# ChromDot_Ring_two_inch.net
KiCad netlist of a schematic drawn in EAGLE
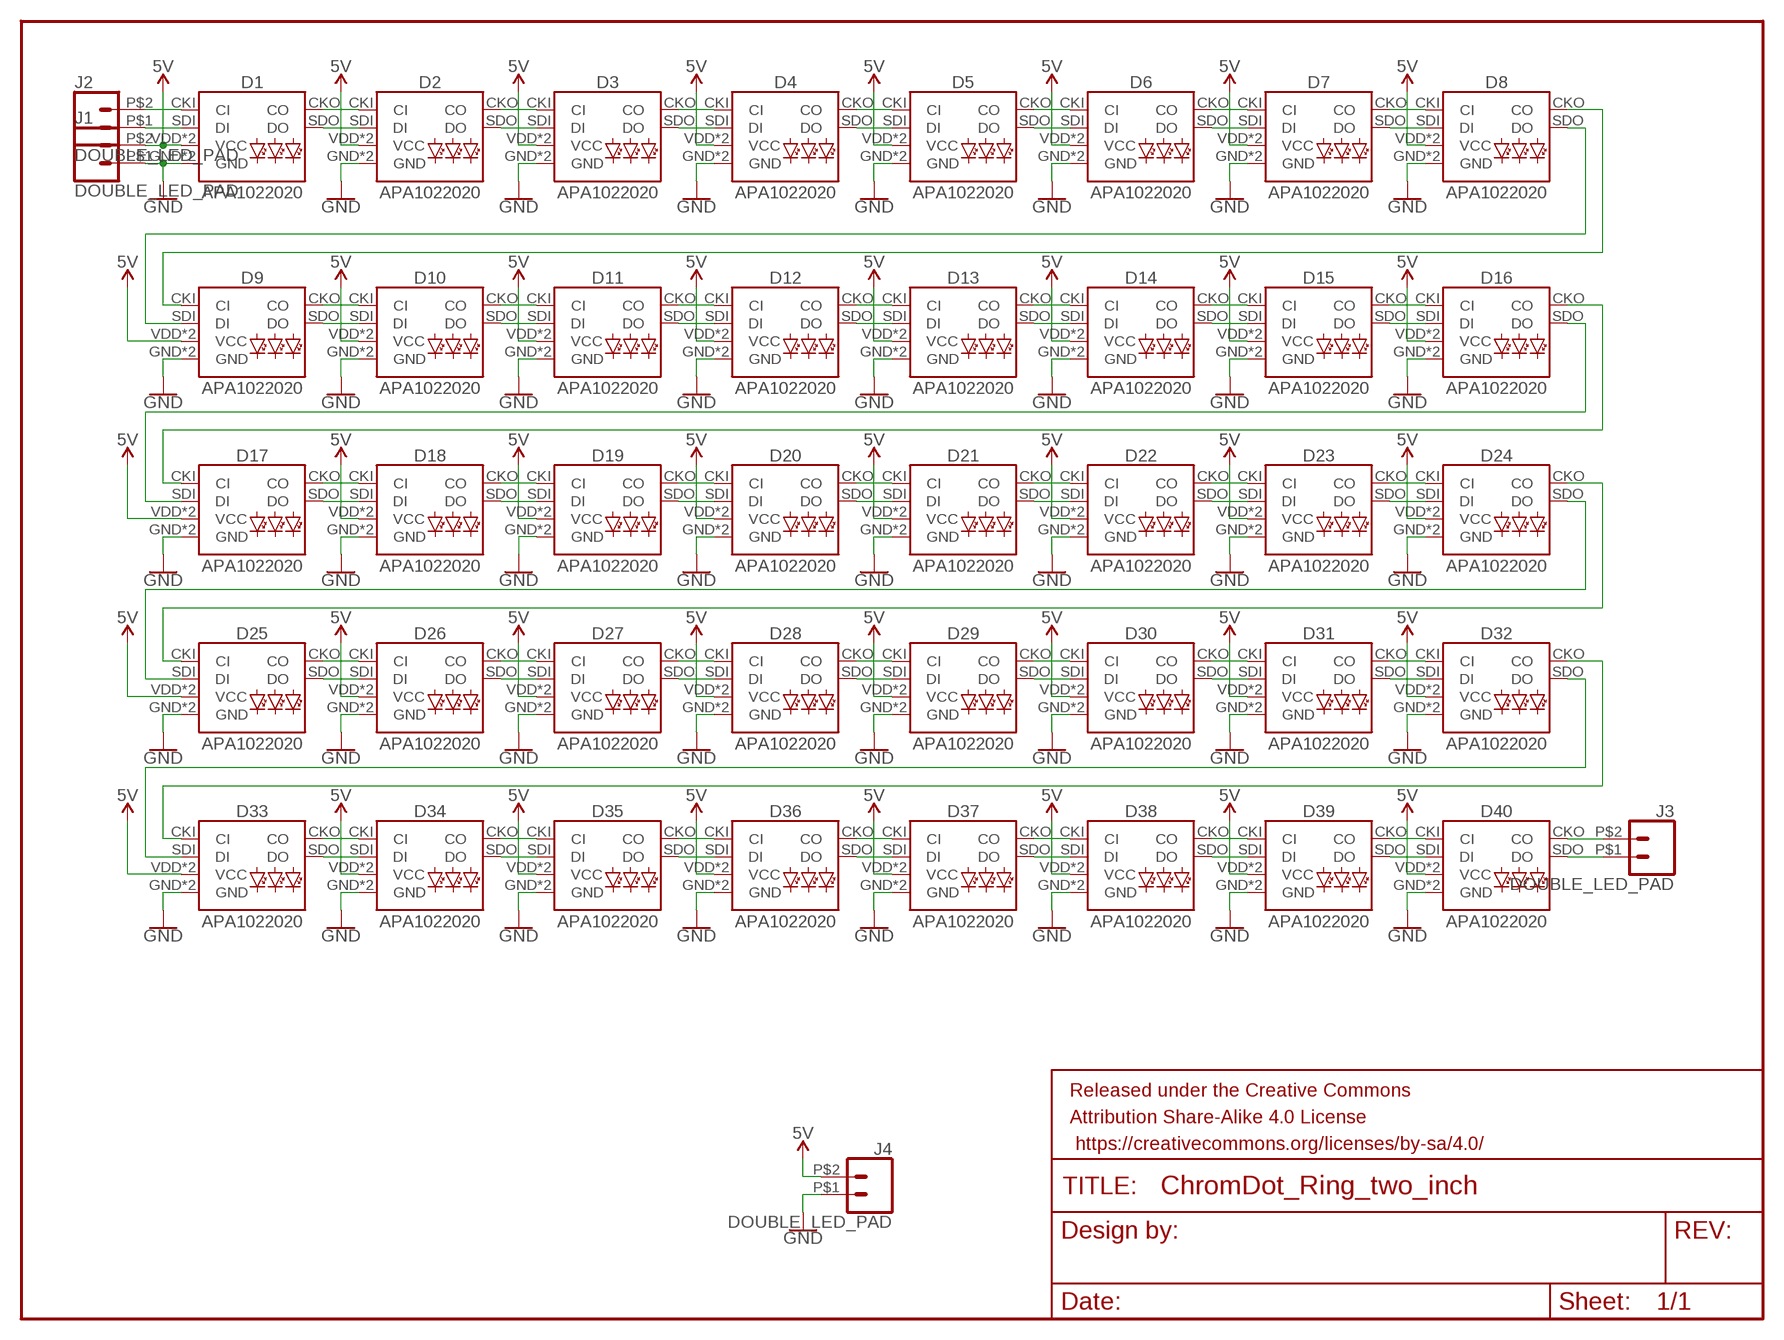
[diagram p0: schematic, sheet 1]

(export (version "E")
  (design (tool "Eeschema 10.0.6"))
  (components
    (comp (ref "D1")
      (value "APA1022020")
      (footprint "eagle-import:APA102-2020")
      (libsource (lib "eagle-import") (part "APA1022020"))
    )
    (comp (ref "D2")
      (value "APA1022020")
      (footprint "eagle-import:APA102-2020")
      (libsource (lib "eagle-import") (part "APA1022020"))
    )
    (comp (ref "D3")
      (value "APA1022020")
      (footprint "eagle-import:APA102-2020")
      (libsource (lib "eagle-import") (part "APA1022020"))
    )
    (comp (ref "D4")
      (value "APA1022020")
      (footprint "eagle-import:APA102-2020")
      (libsource (lib "eagle-import") (part "APA1022020"))
    )
    (comp (ref "D5")
      (value "APA1022020")
      (footprint "eagle-import:APA102-2020")
      (libsource (lib "eagle-import") (part "APA1022020"))
    )
    (comp (ref "D6")
      (value "APA1022020")
      (footprint "eagle-import:APA102-2020")
      (libsource (lib "eagle-import") (part "APA1022020"))
    )
    (comp (ref "D7")
      (value "APA1022020")
      (footprint "eagle-import:APA102-2020")
      (libsource (lib "eagle-import") (part "APA1022020"))
    )
    (comp (ref "D8")
      (value "APA1022020")
      (footprint "eagle-import:APA102-2020")
      (libsource (lib "eagle-import") (part "APA1022020"))
    )
    (comp (ref "D9")
      (value "APA1022020")
      (footprint "eagle-import:APA102-2020")
      (libsource (lib "eagle-import") (part "APA1022020"))
    )
    (comp (ref "D10")
      (value "APA1022020")
      (footprint "eagle-import:APA102-2020")
      (libsource (lib "eagle-import") (part "APA1022020"))
    )
    (comp (ref "D11")
      (value "APA1022020")
      (footprint "eagle-import:APA102-2020")
      (libsource (lib "eagle-import") (part "APA1022020"))
    )
    (comp (ref "D12")
      (value "APA1022020")
      (footprint "eagle-import:APA102-2020")
      (libsource (lib "eagle-import") (part "APA1022020"))
    )
    (comp (ref "D13")
      (value "APA1022020")
      (footprint "eagle-import:APA102-2020")
      (libsource (lib "eagle-import") (part "APA1022020"))
    )
    (comp (ref "D14")
      (value "APA1022020")
      (footprint "eagle-import:APA102-2020")
      (libsource (lib "eagle-import") (part "APA1022020"))
    )
    (comp (ref "D15")
      (value "APA1022020")
      (footprint "eagle-import:APA102-2020")
      (libsource (lib "eagle-import") (part "APA1022020"))
    )
    (comp (ref "D16")
      (value "APA1022020")
      (footprint "eagle-import:APA102-2020")
      (libsource (lib "eagle-import") (part "APA1022020"))
    )
    (comp (ref "D17")
      (value "APA1022020")
      (footprint "eagle-import:APA102-2020")
      (libsource (lib "eagle-import") (part "APA1022020"))
    )
    (comp (ref "D18")
      (value "APA1022020")
      (footprint "eagle-import:APA102-2020")
      (libsource (lib "eagle-import") (part "APA1022020"))
    )
    (comp (ref "D19")
      (value "APA1022020")
      (footprint "eagle-import:APA102-2020")
      (libsource (lib "eagle-import") (part "APA1022020"))
    )
    (comp (ref "D20")
      (value "APA1022020")
      (footprint "eagle-import:APA102-2020")
      (libsource (lib "eagle-import") (part "APA1022020"))
    )
    (comp (ref "D21")
      (value "APA1022020")
      (footprint "eagle-import:APA102-2020")
      (libsource (lib "eagle-import") (part "APA1022020"))
    )
    (comp (ref "D22")
      (value "APA1022020")
      (footprint "eagle-import:APA102-2020")
      (libsource (lib "eagle-import") (part "APA1022020"))
    )
    (comp (ref "D23")
      (value "APA1022020")
      (footprint "eagle-import:APA102-2020")
      (libsource (lib "eagle-import") (part "APA1022020"))
    )
    (comp (ref "D24")
      (value "APA1022020")
      (footprint "eagle-import:APA102-2020")
      (libsource (lib "eagle-import") (part "APA1022020"))
    )
    (comp (ref "D25")
      (value "APA1022020")
      (footprint "eagle-import:APA102-2020")
      (libsource (lib "eagle-import") (part "APA1022020"))
    )
    (comp (ref "D26")
      (value "APA1022020")
      (footprint "eagle-import:APA102-2020")
      (libsource (lib "eagle-import") (part "APA1022020"))
    )
    (comp (ref "D27")
      (value "APA1022020")
      (footprint "eagle-import:APA102-2020")
      (libsource (lib "eagle-import") (part "APA1022020"))
    )
    (comp (ref "D28")
      (value "APA1022020")
      (footprint "eagle-import:APA102-2020")
      (libsource (lib "eagle-import") (part "APA1022020"))
    )
    (comp (ref "D29")
      (value "APA1022020")
      (footprint "eagle-import:APA102-2020")
      (libsource (lib "eagle-import") (part "APA1022020"))
    )
    (comp (ref "D30")
      (value "APA1022020")
      (footprint "eagle-import:APA102-2020")
      (libsource (lib "eagle-import") (part "APA1022020"))
    )
    (comp (ref "D31")
      (value "APA1022020")
      (footprint "eagle-import:APA102-2020")
      (libsource (lib "eagle-import") (part "APA1022020"))
    )
    (comp (ref "D32")
      (value "APA1022020")
      (footprint "eagle-import:APA102-2020")
      (libsource (lib "eagle-import") (part "APA1022020"))
    )
    (comp (ref "D33")
      (value "APA1022020")
      (footprint "eagle-import:APA102-2020")
      (libsource (lib "eagle-import") (part "APA1022020"))
    )
    (comp (ref "D34")
      (value "APA1022020")
      (footprint "eagle-import:APA102-2020")
      (libsource (lib "eagle-import") (part "APA1022020"))
    )
    (comp (ref "D35")
      (value "APA1022020")
      (footprint "eagle-import:APA102-2020")
      (libsource (lib "eagle-import") (part "APA1022020"))
    )
    (comp (ref "D36")
      (value "APA1022020")
      (footprint "eagle-import:APA102-2020")
      (libsource (lib "eagle-import") (part "APA1022020"))
    )
    (comp (ref "D37")
      (value "APA1022020")
      (footprint "eagle-import:APA102-2020")
      (libsource (lib "eagle-import") (part "APA1022020"))
    )
    (comp (ref "D38")
      (value "APA1022020")
      (footprint "eagle-import:APA102-2020")
      (libsource (lib "eagle-import") (part "APA1022020"))
    )
    (comp (ref "D39")
      (value "APA1022020")
      (footprint "eagle-import:APA102-2020")
      (libsource (lib "eagle-import") (part "APA1022020"))
    )
    (comp (ref "D40")
      (value "APA1022020")
      (footprint "eagle-import:APA102-2020")
      (libsource (lib "eagle-import") (part "APA1022020"))
    )
    (comp (ref "FRAME1")
      (value "FRAME-LETTER")
      (footprint "eagle-import:CREATIVE_COMMONS")
      (libsource (lib "eagle-import") (part "FRAME-LETTER"))
    )
    (comp (ref "J1")
      (value "DOUBLE_LED_PAD")
      (footprint "eagle-import:DOUBLELEDPAD")
      (libsource (lib "eagle-import") (part "DOUBLE_LED_PAD"))
    )
    (comp (ref "J2")
      (value "DOUBLE_LED_PAD")
      (footprint "eagle-import:DOUBLELEDPAD")
      (libsource (lib "eagle-import") (part "DOUBLE_LED_PAD"))
    )
    (comp (ref "J3")
      (value "DOUBLE_LED_PAD")
      (footprint "eagle-import:DOUBLELEDPAD")
      (libsource (lib "eagle-import") (part "DOUBLE_LED_PAD"))
    )
    (comp (ref "J4")
      (value "DOUBLE_LED_PAD")
      (footprint "eagle-import:DOUBLELEDPAD")
      (libsource (lib "eagle-import") (part "DOUBLE_LED_PAD"))
    )
  )
  (nets
    (net (code "1") (name "5V") (class "Default")
      (node (ref "D1") (pin "VDD") (pinfunction "VCC_VDD") (pintype "bidirectional"))
      (node (ref "D1") (pin "VDDPAD") (pinfunction "VCC_VDDPAD") (pintype "bidirectional"))
      (node (ref "D10") (pin "VDD") (pinfunction "VCC_VDD") (pintype "bidirectional"))
      (node (ref "D10") (pin "VDDPAD") (pinfunction "VCC_VDDPAD") (pintype "bidirectional"))
      (node (ref "D11") (pin "VDD") (pinfunction "VCC_VDD") (pintype "bidirectional"))
      (node (ref "D11") (pin "VDDPAD") (pinfunction "VCC_VDDPAD") (pintype "bidirectional"))
      (node (ref "D12") (pin "VDD") (pinfunction "VCC_VDD") (pintype "bidirectional"))
      (node (ref "D12") (pin "VDDPAD") (pinfunction "VCC_VDDPAD") (pintype "bidirectional"))
      (node (ref "D13") (pin "VDD") (pinfunction "VCC_VDD") (pintype "bidirectional"))
      (node (ref "D13") (pin "VDDPAD") (pinfunction "VCC_VDDPAD") (pintype "bidirectional"))
      (node (ref "D14") (pin "VDD") (pinfunction "VCC_VDD") (pintype "bidirectional"))
      (node (ref "D14") (pin "VDDPAD") (pinfunction "VCC_VDDPAD") (pintype "bidirectional"))
      (node (ref "D15") (pin "VDD") (pinfunction "VCC_VDD") (pintype "bidirectional"))
      (node (ref "D15") (pin "VDDPAD") (pinfunction "VCC_VDDPAD") (pintype "bidirectional"))
      (node (ref "D16") (pin "VDD") (pinfunction "VCC_VDD") (pintype "bidirectional"))
      (node (ref "D16") (pin "VDDPAD") (pinfunction "VCC_VDDPAD") (pintype "bidirectional"))
      (node (ref "D17") (pin "VDD") (pinfunction "VCC_VDD") (pintype "bidirectional"))
      (node (ref "D17") (pin "VDDPAD") (pinfunction "VCC_VDDPAD") (pintype "bidirectional"))
      (node (ref "D18") (pin "VDD") (pinfunction "VCC_VDD") (pintype "bidirectional"))
      (node (ref "D18") (pin "VDDPAD") (pinfunction "VCC_VDDPAD") (pintype "bidirectional"))
      (node (ref "D19") (pin "VDD") (pinfunction "VCC_VDD") (pintype "bidirectional"))
      (node (ref "D19") (pin "VDDPAD") (pinfunction "VCC_VDDPAD") (pintype "bidirectional"))
      (node (ref "D2") (pin "VDD") (pinfunction "VCC_VDD") (pintype "bidirectional"))
      (node (ref "D2") (pin "VDDPAD") (pinfunction "VCC_VDDPAD") (pintype "bidirectional"))
      (node (ref "D20") (pin "VDD") (pinfunction "VCC_VDD") (pintype "bidirectional"))
      (node (ref "D20") (pin "VDDPAD") (pinfunction "VCC_VDDPAD") (pintype "bidirectional"))
      (node (ref "D21") (pin "VDD") (pinfunction "VCC_VDD") (pintype "bidirectional"))
      (node (ref "D21") (pin "VDDPAD") (pinfunction "VCC_VDDPAD") (pintype "bidirectional"))
      (node (ref "D22") (pin "VDD") (pinfunction "VCC_VDD") (pintype "bidirectional"))
      (node (ref "D22") (pin "VDDPAD") (pinfunction "VCC_VDDPAD") (pintype "bidirectional"))
      (node (ref "D23") (pin "VDD") (pinfunction "VCC_VDD") (pintype "bidirectional"))
      (node (ref "D23") (pin "VDDPAD") (pinfunction "VCC_VDDPAD") (pintype "bidirectional"))
      (node (ref "D24") (pin "VDD") (pinfunction "VCC_VDD") (pintype "bidirectional"))
      (node (ref "D24") (pin "VDDPAD") (pinfunction "VCC_VDDPAD") (pintype "bidirectional"))
      (node (ref "D25") (pin "VDD") (pinfunction "VCC_VDD") (pintype "bidirectional"))
      (node (ref "D25") (pin "VDDPAD") (pinfunction "VCC_VDDPAD") (pintype "bidirectional"))
      (node (ref "D26") (pin "VDD") (pinfunction "VCC_VDD") (pintype "bidirectional"))
      (node (ref "D26") (pin "VDDPAD") (pinfunction "VCC_VDDPAD") (pintype "bidirectional"))
      (node (ref "D27") (pin "VDD") (pinfunction "VCC_VDD") (pintype "bidirectional"))
      (node (ref "D27") (pin "VDDPAD") (pinfunction "VCC_VDDPAD") (pintype "bidirectional"))
      (node (ref "D28") (pin "VDD") (pinfunction "VCC_VDD") (pintype "bidirectional"))
      (node (ref "D28") (pin "VDDPAD") (pinfunction "VCC_VDDPAD") (pintype "bidirectional"))
      (node (ref "D29") (pin "VDD") (pinfunction "VCC_VDD") (pintype "bidirectional"))
      (node (ref "D29") (pin "VDDPAD") (pinfunction "VCC_VDDPAD") (pintype "bidirectional"))
      (node (ref "D3") (pin "VDD") (pinfunction "VCC_VDD") (pintype "bidirectional"))
      (node (ref "D3") (pin "VDDPAD") (pinfunction "VCC_VDDPAD") (pintype "bidirectional"))
      (node (ref "D30") (pin "VDD") (pinfunction "VCC_VDD") (pintype "bidirectional"))
      (node (ref "D30") (pin "VDDPAD") (pinfunction "VCC_VDDPAD") (pintype "bidirectional"))
      (node (ref "D31") (pin "VDD") (pinfunction "VCC_VDD") (pintype "bidirectional"))
      (node (ref "D31") (pin "VDDPAD") (pinfunction "VCC_VDDPAD") (pintype "bidirectional"))
      (node (ref "D32") (pin "VDD") (pinfunction "VCC_VDD") (pintype "bidirectional"))
      (node (ref "D32") (pin "VDDPAD") (pinfunction "VCC_VDDPAD") (pintype "bidirectional"))
      (node (ref "D33") (pin "VDD") (pinfunction "VCC_VDD") (pintype "bidirectional"))
      (node (ref "D33") (pin "VDDPAD") (pinfunction "VCC_VDDPAD") (pintype "bidirectional"))
      (node (ref "D34") (pin "VDD") (pinfunction "VCC_VDD") (pintype "bidirectional"))
      (node (ref "D34") (pin "VDDPAD") (pinfunction "VCC_VDDPAD") (pintype "bidirectional"))
      (node (ref "D35") (pin "VDD") (pinfunction "VCC_VDD") (pintype "bidirectional"))
      (node (ref "D35") (pin "VDDPAD") (pinfunction "VCC_VDDPAD") (pintype "bidirectional"))
      (node (ref "D36") (pin "VDD") (pinfunction "VCC_VDD") (pintype "bidirectional"))
      (node (ref "D36") (pin "VDDPAD") (pinfunction "VCC_VDDPAD") (pintype "bidirectional"))
      (node (ref "D37") (pin "VDD") (pinfunction "VCC_VDD") (pintype "bidirectional"))
      (node (ref "D37") (pin "VDDPAD") (pinfunction "VCC_VDDPAD") (pintype "bidirectional"))
      (node (ref "D38") (pin "VDD") (pinfunction "VCC_VDD") (pintype "bidirectional"))
      (node (ref "D38") (pin "VDDPAD") (pinfunction "VCC_VDDPAD") (pintype "bidirectional"))
      (node (ref "D39") (pin "VDD") (pinfunction "VCC_VDD") (pintype "bidirectional"))
      (node (ref "D39") (pin "VDDPAD") (pinfunction "VCC_VDDPAD") (pintype "bidirectional"))
      (node (ref "D4") (pin "VDD") (pinfunction "VCC_VDD") (pintype "bidirectional"))
      (node (ref "D4") (pin "VDDPAD") (pinfunction "VCC_VDDPAD") (pintype "bidirectional"))
      (node (ref "D40") (pin "VDD") (pinfunction "VCC_VDD") (pintype "bidirectional"))
      (node (ref "D40") (pin "VDDPAD") (pinfunction "VCC_VDDPAD") (pintype "bidirectional"))
      (node (ref "D5") (pin "VDD") (pinfunction "VCC_VDD") (pintype "bidirectional"))
      (node (ref "D5") (pin "VDDPAD") (pinfunction "VCC_VDDPAD") (pintype "bidirectional"))
      (node (ref "D6") (pin "VDD") (pinfunction "VCC_VDD") (pintype "bidirectional"))
      (node (ref "D6") (pin "VDDPAD") (pinfunction "VCC_VDDPAD") (pintype "bidirectional"))
      (node (ref "D7") (pin "VDD") (pinfunction "VCC_VDD") (pintype "bidirectional"))
      (node (ref "D7") (pin "VDDPAD") (pinfunction "VCC_VDDPAD") (pintype "bidirectional"))
      (node (ref "D8") (pin "VDD") (pinfunction "VCC_VDD") (pintype "bidirectional"))
      (node (ref "D8") (pin "VDDPAD") (pinfunction "VCC_VDDPAD") (pintype "bidirectional"))
      (node (ref "D9") (pin "VDD") (pinfunction "VCC_VDD") (pintype "bidirectional"))
      (node (ref "D9") (pin "VDDPAD") (pinfunction "VCC_VDDPAD") (pintype "bidirectional"))
      (node (ref "J1") (pin "P$2") (pinfunction "2_P$2") (pintype "passive"))
      (node (ref "J4") (pin "P$2") (pinfunction "2_P$2") (pintype "passive"))
    )
    (net (code "2") (name "GND") (class "Default")
      (node (ref "D1") (pin "GND") (pinfunction "GND_GND") (pintype "bidirectional"))
      (node (ref "D1") (pin "GNDPAD") (pinfunction "GND_GNDPAD") (pintype "bidirectional"))
      (node (ref "D10") (pin "GND") (pinfunction "GND_GND") (pintype "bidirectional"))
      (node (ref "D10") (pin "GNDPAD") (pinfunction "GND_GNDPAD") (pintype "bidirectional"))
      (node (ref "D11") (pin "GND") (pinfunction "GND_GND") (pintype "bidirectional"))
      (node (ref "D11") (pin "GNDPAD") (pinfunction "GND_GNDPAD") (pintype "bidirectional"))
      (node (ref "D12") (pin "GND") (pinfunction "GND_GND") (pintype "bidirectional"))
      (node (ref "D12") (pin "GNDPAD") (pinfunction "GND_GNDPAD") (pintype "bidirectional"))
      (node (ref "D13") (pin "GND") (pinfunction "GND_GND") (pintype "bidirectional"))
      (node (ref "D13") (pin "GNDPAD") (pinfunction "GND_GNDPAD") (pintype "bidirectional"))
      (node (ref "D14") (pin "GND") (pinfunction "GND_GND") (pintype "bidirectional"))
      (node (ref "D14") (pin "GNDPAD") (pinfunction "GND_GNDPAD") (pintype "bidirectional"))
      (node (ref "D15") (pin "GND") (pinfunction "GND_GND") (pintype "bidirectional"))
      (node (ref "D15") (pin "GNDPAD") (pinfunction "GND_GNDPAD") (pintype "bidirectional"))
      (node (ref "D16") (pin "GND") (pinfunction "GND_GND") (pintype "bidirectional"))
      (node (ref "D16") (pin "GNDPAD") (pinfunction "GND_GNDPAD") (pintype "bidirectional"))
      (node (ref "D17") (pin "GND") (pinfunction "GND_GND") (pintype "bidirectional"))
      (node (ref "D17") (pin "GNDPAD") (pinfunction "GND_GNDPAD") (pintype "bidirectional"))
      (node (ref "D18") (pin "GND") (pinfunction "GND_GND") (pintype "bidirectional"))
      (node (ref "D18") (pin "GNDPAD") (pinfunction "GND_GNDPAD") (pintype "bidirectional"))
      (node (ref "D19") (pin "GND") (pinfunction "GND_GND") (pintype "bidirectional"))
      (node (ref "D19") (pin "GNDPAD") (pinfunction "GND_GNDPAD") (pintype "bidirectional"))
      (node (ref "D2") (pin "GND") (pinfunction "GND_GND") (pintype "bidirectional"))
      (node (ref "D2") (pin "GNDPAD") (pinfunction "GND_GNDPAD") (pintype "bidirectional"))
      (node (ref "D20") (pin "GND") (pinfunction "GND_GND") (pintype "bidirectional"))
      (node (ref "D20") (pin "GNDPAD") (pinfunction "GND_GNDPAD") (pintype "bidirectional"))
      (node (ref "D21") (pin "GND") (pinfunction "GND_GND") (pintype "bidirectional"))
      (node (ref "D21") (pin "GNDPAD") (pinfunction "GND_GNDPAD") (pintype "bidirectional"))
      (node (ref "D22") (pin "GND") (pinfunction "GND_GND") (pintype "bidirectional"))
      (node (ref "D22") (pin "GNDPAD") (pinfunction "GND_GNDPAD") (pintype "bidirectional"))
      (node (ref "D23") (pin "GND") (pinfunction "GND_GND") (pintype "bidirectional"))
      (node (ref "D23") (pin "GNDPAD") (pinfunction "GND_GNDPAD") (pintype "bidirectional"))
      (node (ref "D24") (pin "GND") (pinfunction "GND_GND") (pintype "bidirectional"))
      (node (ref "D24") (pin "GNDPAD") (pinfunction "GND_GNDPAD") (pintype "bidirectional"))
      (node (ref "D25") (pin "GND") (pinfunction "GND_GND") (pintype "bidirectional"))
      (node (ref "D25") (pin "GNDPAD") (pinfunction "GND_GNDPAD") (pintype "bidirectional"))
      (node (ref "D26") (pin "GND") (pinfunction "GND_GND") (pintype "bidirectional"))
      (node (ref "D26") (pin "GNDPAD") (pinfunction "GND_GNDPAD") (pintype "bidirectional"))
      (node (ref "D27") (pin "GND") (pinfunction "GND_GND") (pintype "bidirectional"))
      (node (ref "D27") (pin "GNDPAD") (pinfunction "GND_GNDPAD") (pintype "bidirectional"))
      (node (ref "D28") (pin "GND") (pinfunction "GND_GND") (pintype "bidirectional"))
      (node (ref "D28") (pin "GNDPAD") (pinfunction "GND_GNDPAD") (pintype "bidirectional"))
      (node (ref "D29") (pin "GND") (pinfunction "GND_GND") (pintype "bidirectional"))
      (node (ref "D29") (pin "GNDPAD") (pinfunction "GND_GNDPAD") (pintype "bidirectional"))
      (node (ref "D3") (pin "GND") (pinfunction "GND_GND") (pintype "bidirectional"))
      (node (ref "D3") (pin "GNDPAD") (pinfunction "GND_GNDPAD") (pintype "bidirectional"))
      (node (ref "D30") (pin "GND") (pinfunction "GND_GND") (pintype "bidirectional"))
      (node (ref "D30") (pin "GNDPAD") (pinfunction "GND_GNDPAD") (pintype "bidirectional"))
      (node (ref "D31") (pin "GND") (pinfunction "GND_GND") (pintype "bidirectional"))
      (node (ref "D31") (pin "GNDPAD") (pinfunction "GND_GNDPAD") (pintype "bidirectional"))
      (node (ref "D32") (pin "GND") (pinfunction "GND_GND") (pintype "bidirectional"))
      (node (ref "D32") (pin "GNDPAD") (pinfunction "GND_GNDPAD") (pintype "bidirectional"))
      (node (ref "D33") (pin "GND") (pinfunction "GND_GND") (pintype "bidirectional"))
      (node (ref "D33") (pin "GNDPAD") (pinfunction "GND_GNDPAD") (pintype "bidirectional"))
      (node (ref "D34") (pin "GND") (pinfunction "GND_GND") (pintype "bidirectional"))
      (node (ref "D34") (pin "GNDPAD") (pinfunction "GND_GNDPAD") (pintype "bidirectional"))
      (node (ref "D35") (pin "GND") (pinfunction "GND_GND") (pintype "bidirectional"))
      (node (ref "D35") (pin "GNDPAD") (pinfunction "GND_GNDPAD") (pintype "bidirectional"))
      (node (ref "D36") (pin "GND") (pinfunction "GND_GND") (pintype "bidirectional"))
      (node (ref "D36") (pin "GNDPAD") (pinfunction "GND_GNDPAD") (pintype "bidirectional"))
      (node (ref "D37") (pin "GND") (pinfunction "GND_GND") (pintype "bidirectional"))
      (node (ref "D37") (pin "GNDPAD") (pinfunction "GND_GNDPAD") (pintype "bidirectional"))
      (node (ref "D38") (pin "GND") (pinfunction "GND_GND") (pintype "bidirectional"))
      (node (ref "D38") (pin "GNDPAD") (pinfunction "GND_GNDPAD") (pintype "bidirectional"))
      (node (ref "D39") (pin "GND") (pinfunction "GND_GND") (pintype "bidirectional"))
      (node (ref "D39") (pin "GNDPAD") (pinfunction "GND_GNDPAD") (pintype "bidirectional"))
      (node (ref "D4") (pin "GND") (pinfunction "GND_GND") (pintype "bidirectional"))
      (node (ref "D4") (pin "GNDPAD") (pinfunction "GND_GNDPAD") (pintype "bidirectional"))
      (node (ref "D40") (pin "GND") (pinfunction "GND_GND") (pintype "bidirectional"))
      (node (ref "D40") (pin "GNDPAD") (pinfunction "GND_GNDPAD") (pintype "bidirectional"))
      (node (ref "D5") (pin "GND") (pinfunction "GND_GND") (pintype "bidirectional"))
      (node (ref "D5") (pin "GNDPAD") (pinfunction "GND_GNDPAD") (pintype "bidirectional"))
      (node (ref "D6") (pin "GND") (pinfunction "GND_GND") (pintype "bidirectional"))
      (node (ref "D6") (pin "GNDPAD") (pinfunction "GND_GNDPAD") (pintype "bidirectional"))
      (node (ref "D7") (pin "GND") (pinfunction "GND_GND") (pintype "bidirectional"))
      (node (ref "D7") (pin "GNDPAD") (pinfunction "GND_GNDPAD") (pintype "bidirectional"))
      (node (ref "D8") (pin "GND") (pinfunction "GND_GND") (pintype "bidirectional"))
      (node (ref "D8") (pin "GNDPAD") (pinfunction "GND_GNDPAD") (pintype "bidirectional"))
      (node (ref "D9") (pin "GND") (pinfunction "GND_GND") (pintype "bidirectional"))
      (node (ref "D9") (pin "GNDPAD") (pinfunction "GND_GNDPAD") (pintype "bidirectional"))
      (node (ref "J1") (pin "P$1") (pinfunction "1_P$1") (pintype "passive"))
      (node (ref "J4") (pin "P$1") (pinfunction "1_P$1") (pintype "passive"))
    )
    (net (code "3") (name "Net-(D1-CI)") (class "Default")
      (node (ref "D1") (pin "CKI") (pinfunction "CI_CKI") (pintype "bidirectional"))
      (node (ref "J2") (pin "P$2") (pinfunction "2_P$2") (pintype "passive"))
    )
    (net (code "4") (name "Net-(D1-CO)") (class "Default")
      (node (ref "D1") (pin "CKO") (pinfunction "CO_CKO") (pintype "bidirectional"))
      (node (ref "D2") (pin "CKI") (pinfunction "CI_CKI") (pintype "bidirectional"))
    )
    (net (code "5") (name "Net-(D1-DI)") (class "Default")
      (node (ref "D1") (pin "SDI") (pinfunction "DI_SDI") (pintype "bidirectional"))
      (node (ref "J2") (pin "P$1") (pinfunction "1_P$1") (pintype "passive"))
    )
    (net (code "6") (name "Net-(D1-DO)") (class "Default")
      (node (ref "D1") (pin "SDO") (pinfunction "DO_SDO") (pintype "bidirectional"))
      (node (ref "D2") (pin "SDI") (pinfunction "DI_SDI") (pintype "bidirectional"))
    )
    (net (code "7") (name "Net-(D2-CO)") (class "Default")
      (node (ref "D2") (pin "CKO") (pinfunction "CO_CKO") (pintype "bidirectional"))
      (node (ref "D3") (pin "CKI") (pinfunction "CI_CKI") (pintype "bidirectional"))
    )
    (net (code "8") (name "Net-(D2-DO)") (class "Default")
      (node (ref "D2") (pin "SDO") (pinfunction "DO_SDO") (pintype "bidirectional"))
      (node (ref "D3") (pin "SDI") (pinfunction "DI_SDI") (pintype "bidirectional"))
    )
    (net (code "9") (name "Net-(D3-CO)") (class "Default")
      (node (ref "D3") (pin "CKO") (pinfunction "CO_CKO") (pintype "bidirectional"))
      (node (ref "D4") (pin "CKI") (pinfunction "CI_CKI") (pintype "bidirectional"))
    )
    (net (code "10") (name "Net-(D3-DO)") (class "Default")
      (node (ref "D3") (pin "SDO") (pinfunction "DO_SDO") (pintype "bidirectional"))
      (node (ref "D4") (pin "SDI") (pinfunction "DI_SDI") (pintype "bidirectional"))
    )
    (net (code "11") (name "Net-(D4-CO)") (class "Default")
      (node (ref "D4") (pin "CKO") (pinfunction "CO_CKO") (pintype "bidirectional"))
      (node (ref "D5") (pin "CKI") (pinfunction "CI_CKI") (pintype "bidirectional"))
    )
    (net (code "12") (name "Net-(D4-DO)") (class "Default")
      (node (ref "D4") (pin "SDO") (pinfunction "DO_SDO") (pintype "bidirectional"))
      (node (ref "D5") (pin "SDI") (pinfunction "DI_SDI") (pintype "bidirectional"))
    )
    (net (code "13") (name "Net-(D5-CO)") (class "Default")
      (node (ref "D5") (pin "CKO") (pinfunction "CO_CKO") (pintype "bidirectional"))
      (node (ref "D6") (pin "CKI") (pinfunction "CI_CKI") (pintype "bidirectional"))
    )
    (net (code "14") (name "Net-(D5-DO)") (class "Default")
      (node (ref "D5") (pin "SDO") (pinfunction "DO_SDO") (pintype "bidirectional"))
      (node (ref "D6") (pin "SDI") (pinfunction "DI_SDI") (pintype "bidirectional"))
    )
    (net (code "15") (name "Net-(D6-CO)") (class "Default")
      (node (ref "D6") (pin "CKO") (pinfunction "CO_CKO") (pintype "bidirectional"))
      (node (ref "D7") (pin "CKI") (pinfunction "CI_CKI") (pintype "bidirectional"))
    )
    (net (code "16") (name "Net-(D6-DO)") (class "Default")
      (node (ref "D6") (pin "SDO") (pinfunction "DO_SDO") (pintype "bidirectional"))
      (node (ref "D7") (pin "SDI") (pinfunction "DI_SDI") (pintype "bidirectional"))
    )
    (net (code "17") (name "Net-(D7-CO)") (class "Default")
      (node (ref "D7") (pin "CKO") (pinfunction "CO_CKO") (pintype "bidirectional"))
      (node (ref "D8") (pin "CKI") (pinfunction "CI_CKI") (pintype "bidirectional"))
    )
    (net (code "18") (name "Net-(D7-DO)") (class "Default")
      (node (ref "D7") (pin "SDO") (pinfunction "DO_SDO") (pintype "bidirectional"))
      (node (ref "D8") (pin "SDI") (pinfunction "DI_SDI") (pintype "bidirectional"))
    )
    (net (code "19") (name "Net-(D8-CO)") (class "Default")
      (node (ref "D8") (pin "CKO") (pinfunction "CO_CKO") (pintype "bidirectional"))
      (node (ref "D9") (pin "CKI") (pinfunction "CI_CKI") (pintype "bidirectional"))
    )
    (net (code "20") (name "Net-(D8-DO)") (class "Default")
      (node (ref "D8") (pin "SDO") (pinfunction "DO_SDO") (pintype "bidirectional"))
      (node (ref "D9") (pin "SDI") (pinfunction "DI_SDI") (pintype "bidirectional"))
    )
    (net (code "21") (name "Net-(D10-CI)") (class "Default")
      (node (ref "D10") (pin "CKI") (pinfunction "CI_CKI") (pintype "bidirectional"))
      (node (ref "D9") (pin "CKO") (pinfunction "CO_CKO") (pintype "bidirectional"))
    )
    (net (code "22") (name "Net-(D10-CO)") (class "Default")
      (node (ref "D10") (pin "CKO") (pinfunction "CO_CKO") (pintype "bidirectional"))
      (node (ref "D11") (pin "CKI") (pinfunction "CI_CKI") (pintype "bidirectional"))
    )
    (net (code "23") (name "Net-(D10-DI)") (class "Default")
      (node (ref "D10") (pin "SDI") (pinfunction "DI_SDI") (pintype "bidirectional"))
      (node (ref "D9") (pin "SDO") (pinfunction "DO_SDO") (pintype "bidirectional"))
    )
    (net (code "24") (name "Net-(D10-DO)") (class "Default")
      (node (ref "D10") (pin "SDO") (pinfunction "DO_SDO") (pintype "bidirectional"))
      (node (ref "D11") (pin "SDI") (pinfunction "DI_SDI") (pintype "bidirectional"))
    )
    (net (code "25") (name "Net-(D11-CO)") (class "Default")
      (node (ref "D11") (pin "CKO") (pinfunction "CO_CKO") (pintype "bidirectional"))
      (node (ref "D12") (pin "CKI") (pinfunction "CI_CKI") (pintype "bidirectional"))
    )
    (net (code "26") (name "Net-(D11-DO)") (class "Default")
      (node (ref "D11") (pin "SDO") (pinfunction "DO_SDO") (pintype "bidirectional"))
      (node (ref "D12") (pin "SDI") (pinfunction "DI_SDI") (pintype "bidirectional"))
    )
    (net (code "27") (name "Net-(D12-CO)") (class "Default")
      (node (ref "D12") (pin "CKO") (pinfunction "CO_CKO") (pintype "bidirectional"))
      (node (ref "D13") (pin "CKI") (pinfunction "CI_CKI") (pintype "bidirectional"))
    )
    (net (code "28") (name "Net-(D12-DO)") (class "Default")
      (node (ref "D12") (pin "SDO") (pinfunction "DO_SDO") (pintype "bidirectional"))
      (node (ref "D13") (pin "SDI") (pinfunction "DI_SDI") (pintype "bidirectional"))
    )
    (net (code "29") (name "Net-(D13-CO)") (class "Default")
      (node (ref "D13") (pin "CKO") (pinfunction "CO_CKO") (pintype "bidirectional"))
      (node (ref "D14") (pin "CKI") (pinfunction "CI_CKI") (pintype "bidirectional"))
    )
    (net (code "30") (name "Net-(D13-DO)") (class "Default")
      (node (ref "D13") (pin "SDO") (pinfunction "DO_SDO") (pintype "bidirectional"))
      (node (ref "D14") (pin "SDI") (pinfunction "DI_SDI") (pintype "bidirectional"))
    )
    (net (code "31") (name "Net-(D14-CO)") (class "Default")
      (node (ref "D14") (pin "CKO") (pinfunction "CO_CKO") (pintype "bidirectional"))
      (node (ref "D15") (pin "CKI") (pinfunction "CI_CKI") (pintype "bidirectional"))
    )
    (net (code "32") (name "Net-(D14-DO)") (class "Default")
      (node (ref "D14") (pin "SDO") (pinfunction "DO_SDO") (pintype "bidirectional"))
      (node (ref "D15") (pin "SDI") (pinfunction "DI_SDI") (pintype "bidirectional"))
    )
    (net (code "33") (name "Net-(D15-CO)") (class "Default")
      (node (ref "D15") (pin "CKO") (pinfunction "CO_CKO") (pintype "bidirectional"))
      (node (ref "D16") (pin "CKI") (pinfunction "CI_CKI") (pintype "bidirectional"))
    )
    (net (code "34") (name "Net-(D15-DO)") (class "Default")
      (node (ref "D15") (pin "SDO") (pinfunction "DO_SDO") (pintype "bidirectional"))
      (node (ref "D16") (pin "SDI") (pinfunction "DI_SDI") (pintype "bidirectional"))
    )
    (net (code "35") (name "Net-(D16-CO)") (class "Default")
      (node (ref "D16") (pin "CKO") (pinfunction "CO_CKO") (pintype "bidirectional"))
      (node (ref "D17") (pin "CKI") (pinfunction "CI_CKI") (pintype "bidirectional"))
    )
    (net (code "36") (name "Net-(D16-DO)") (class "Default")
      (node (ref "D16") (pin "SDO") (pinfunction "DO_SDO") (pintype "bidirectional"))
      (node (ref "D17") (pin "SDI") (pinfunction "DI_SDI") (pintype "bidirectional"))
    )
    (net (code "37") (name "Net-(D17-CO)") (class "Default")
      (node (ref "D17") (pin "CKO") (pinfunction "CO_CKO") (pintype "bidirectional"))
      (node (ref "D18") (pin "CKI") (pinfunction "CI_CKI") (pintype "bidirectional"))
    )
    (net (code "38") (name "Net-(D17-DO)") (class "Default")
      (node (ref "D17") (pin "SDO") (pinfunction "DO_SDO") (pintype "bidirectional"))
      (node (ref "D18") (pin "SDI") (pinfunction "DI_SDI") (pintype "bidirectional"))
    )
    (net (code "39") (name "Net-(D18-CO)") (class "Default")
      (node (ref "D18") (pin "CKO") (pinfunction "CO_CKO") (pintype "bidirectional"))
      (node (ref "D19") (pin "CKI") (pinfunction "CI_CKI") (pintype "bidirectional"))
    )
    (net (code "40") (name "Net-(D18-DO)") (class "Default")
      (node (ref "D18") (pin "SDO") (pinfunction "DO_SDO") (pintype "bidirectional"))
      (node (ref "D19") (pin "SDI") (pinfunction "DI_SDI") (pintype "bidirectional"))
    )
    (net (code "41") (name "Net-(D19-CO)") (class "Default")
      (node (ref "D19") (pin "CKO") (pinfunction "CO_CKO") (pintype "bidirectional"))
      (node (ref "D20") (pin "CKI") (pinfunction "CI_CKI") (pintype "bidirectional"))
    )
    (net (code "42") (name "Net-(D19-DO)") (class "Default")
      (node (ref "D19") (pin "SDO") (pinfunction "DO_SDO") (pintype "bidirectional"))
      (node (ref "D20") (pin "SDI") (pinfunction "DI_SDI") (pintype "bidirectional"))
    )
    (net (code "43") (name "Net-(D20-CO)") (class "Default")
      (node (ref "D20") (pin "CKO") (pinfunction "CO_CKO") (pintype "bidirectional"))
      (node (ref "D21") (pin "CKI") (pinfunction "CI_CKI") (pintype "bidirectional"))
    )
    (net (code "44") (name "Net-(D20-DO)") (class "Default")
      (node (ref "D20") (pin "SDO") (pinfunction "DO_SDO") (pintype "bidirectional"))
      (node (ref "D21") (pin "SDI") (pinfunction "DI_SDI") (pintype "bidirectional"))
    )
    (net (code "45") (name "Net-(D21-CO)") (class "Default")
      (node (ref "D21") (pin "CKO") (pinfunction "CO_CKO") (pintype "bidirectional"))
      (node (ref "D22") (pin "CKI") (pinfunction "CI_CKI") (pintype "bidirectional"))
    )
    (net (code "46") (name "Net-(D21-DO)") (class "Default")
      (node (ref "D21") (pin "SDO") (pinfunction "DO_SDO") (pintype "bidirectional"))
      (node (ref "D22") (pin "SDI") (pinfunction "DI_SDI") (pintype "bidirectional"))
    )
    (net (code "47") (name "Net-(D22-CO)") (class "Default")
      (node (ref "D22") (pin "CKO") (pinfunction "CO_CKO") (pintype "bidirectional"))
      (node (ref "D23") (pin "CKI") (pinfunction "CI_CKI") (pintype "bidirectional"))
    )
    (net (code "48") (name "Net-(D22-DO)") (class "Default")
      (node (ref "D22") (pin "SDO") (pinfunction "DO_SDO") (pintype "bidirectional"))
      (node (ref "D23") (pin "SDI") (pinfunction "DI_SDI") (pintype "bidirectional"))
    )
    (net (code "49") (name "Net-(D23-CO)") (class "Default")
      (node (ref "D23") (pin "CKO") (pinfunction "CO_CKO") (pintype "bidirectional"))
      (node (ref "D24") (pin "CKI") (pinfunction "CI_CKI") (pintype "bidirectional"))
    )
    (net (code "50") (name "Net-(D23-DO)") (class "Default")
      (node (ref "D23") (pin "SDO") (pinfunction "DO_SDO") (pintype "bidirectional"))
      (node (ref "D24") (pin "SDI") (pinfunction "DI_SDI") (pintype "bidirectional"))
    )
    (net (code "51") (name "Net-(D24-CO)") (class "Default")
      (node (ref "D24") (pin "CKO") (pinfunction "CO_CKO") (pintype "bidirectional"))
      (node (ref "D25") (pin "CKI") (pinfunction "CI_CKI") (pintype "bidirectional"))
    )
    (net (code "52") (name "Net-(D24-DO)") (class "Default")
      (node (ref "D24") (pin "SDO") (pinfunction "DO_SDO") (pintype "bidirectional"))
      (node (ref "D25") (pin "SDI") (pinfunction "DI_SDI") (pintype "bidirectional"))
    )
    (net (code "53") (name "Net-(D25-CO)") (class "Default")
      (node (ref "D25") (pin "CKO") (pinfunction "CO_CKO") (pintype "bidirectional"))
      (node (ref "D26") (pin "CKI") (pinfunction "CI_CKI") (pintype "bidirectional"))
    )
    (net (code "54") (name "Net-(D25-DO)") (class "Default")
      (node (ref "D25") (pin "SDO") (pinfunction "DO_SDO") (pintype "bidirectional"))
      (node (ref "D26") (pin "SDI") (pinfunction "DI_SDI") (pintype "bidirectional"))
    )
    (net (code "55") (name "Net-(D26-CO)") (class "Default")
      (node (ref "D26") (pin "CKO") (pinfunction "CO_CKO") (pintype "bidirectional"))
      (node (ref "D27") (pin "CKI") (pinfunction "CI_CKI") (pintype "bidirectional"))
    )
    (net (code "56") (name "Net-(D26-DO)") (class "Default")
      (node (ref "D26") (pin "SDO") (pinfunction "DO_SDO") (pintype "bidirectional"))
      (node (ref "D27") (pin "SDI") (pinfunction "DI_SDI") (pintype "bidirectional"))
    )
    (net (code "57") (name "Net-(D27-CO)") (class "Default")
      (node (ref "D27") (pin "CKO") (pinfunction "CO_CKO") (pintype "bidirectional"))
      (node (ref "D28") (pin "CKI") (pinfunction "CI_CKI") (pintype "bidirectional"))
    )
    (net (code "58") (name "Net-(D27-DO)") (class "Default")
      (node (ref "D27") (pin "SDO") (pinfunction "DO_SDO") (pintype "bidirectional"))
      (node (ref "D28") (pin "SDI") (pinfunction "DI_SDI") (pintype "bidirectional"))
    )
    (net (code "59") (name "Net-(D28-CO)") (class "Default")
      (node (ref "D28") (pin "CKO") (pinfunction "CO_CKO") (pintype "bidirectional"))
      (node (ref "D29") (pin "CKI") (pinfunction "CI_CKI") (pintype "bidirectional"))
    )
    (net (code "60") (name "Net-(D28-DO)") (class "Default")
      (node (ref "D28") (pin "SDO") (pinfunction "DO_SDO") (pintype "bidirectional"))
      (node (ref "D29") (pin "SDI") (pinfunction "DI_SDI") (pintype "bidirectional"))
    )
    (net (code "61") (name "Net-(D29-CO)") (class "Default")
      (node (ref "D29") (pin "CKO") (pinfunction "CO_CKO") (pintype "bidirectional"))
      (node (ref "D30") (pin "CKI") (pinfunction "CI_CKI") (pintype "bidirectional"))
    )
    (net (code "62") (name "Net-(D29-DO)") (class "Default")
      (node (ref "D29") (pin "SDO") (pinfunction "DO_SDO") (pintype "bidirectional"))
      (node (ref "D30") (pin "SDI") (pinfunction "DI_SDI") (pintype "bidirectional"))
    )
    (net (code "63") (name "Net-(D30-CO)") (class "Default")
      (node (ref "D30") (pin "CKO") (pinfunction "CO_CKO") (pintype "bidirectional"))
      (node (ref "D31") (pin "CKI") (pinfunction "CI_CKI") (pintype "bidirectional"))
    )
    (net (code "64") (name "Net-(D30-DO)") (class "Default")
      (node (ref "D30") (pin "SDO") (pinfunction "DO_SDO") (pintype "bidirectional"))
      (node (ref "D31") (pin "SDI") (pinfunction "DI_SDI") (pintype "bidirectional"))
    )
    (net (code "65") (name "Net-(D31-CO)") (class "Default")
      (node (ref "D31") (pin "CKO") (pinfunction "CO_CKO") (pintype "bidirectional"))
      (node (ref "D32") (pin "CKI") (pinfunction "CI_CKI") (pintype "bidirectional"))
    )
    (net (code "66") (name "Net-(D31-DO)") (class "Default")
      (node (ref "D31") (pin "SDO") (pinfunction "DO_SDO") (pintype "bidirectional"))
      (node (ref "D32") (pin "SDI") (pinfunction "DI_SDI") (pintype "bidirectional"))
    )
    (net (code "67") (name "Net-(D32-CO)") (class "Default")
      (node (ref "D32") (pin "CKO") (pinfunction "CO_CKO") (pintype "bidirectional"))
      (node (ref "D33") (pin "CKI") (pinfunction "CI_CKI") (pintype "bidirectional"))
    )
    (net (code "68") (name "Net-(D32-DO)") (class "Default")
      (node (ref "D32") (pin "SDO") (pinfunction "DO_SDO") (pintype "bidirectional"))
      (node (ref "D33") (pin "SDI") (pinfunction "DI_SDI") (pintype "bidirectional"))
    )
    (net (code "69") (name "Net-(D33-CO)") (class "Default")
      (node (ref "D33") (pin "CKO") (pinfunction "CO_CKO") (pintype "bidirectional"))
      (node (ref "D34") (pin "CKI") (pinfunction "CI_CKI") (pintype "bidirectional"))
    )
    (net (code "70") (name "Net-(D33-DO)") (class "Default")
      (node (ref "D33") (pin "SDO") (pinfunction "DO_SDO") (pintype "bidirectional"))
      (node (ref "D34") (pin "SDI") (pinfunction "DI_SDI") (pintype "bidirectional"))
    )
    (net (code "71") (name "Net-(D34-CO)") (class "Default")
      (node (ref "D34") (pin "CKO") (pinfunction "CO_CKO") (pintype "bidirectional"))
      (node (ref "D35") (pin "CKI") (pinfunction "CI_CKI") (pintype "bidirectional"))
    )
    (net (code "72") (name "Net-(D34-DO)") (class "Default")
      (node (ref "D34") (pin "SDO") (pinfunction "DO_SDO") (pintype "bidirectional"))
      (node (ref "D35") (pin "SDI") (pinfunction "DI_SDI") (pintype "bidirectional"))
    )
    (net (code "73") (name "Net-(D35-CO)") (class "Default")
      (node (ref "D35") (pin "CKO") (pinfunction "CO_CKO") (pintype "bidirectional"))
      (node (ref "D36") (pin "CKI") (pinfunction "CI_CKI") (pintype "bidirectional"))
    )
    (net (code "74") (name "Net-(D35-DO)") (class "Default")
      (node (ref "D35") (pin "SDO") (pinfunction "DO_SDO") (pintype "bidirectional"))
      (node (ref "D36") (pin "SDI") (pinfunction "DI_SDI") (pintype "bidirectional"))
    )
    (net (code "75") (name "Net-(D36-CO)") (class "Default")
      (node (ref "D36") (pin "CKO") (pinfunction "CO_CKO") (pintype "bidirectional"))
      (node (ref "D37") (pin "CKI") (pinfunction "CI_CKI") (pintype "bidirectional"))
    )
    (net (code "76") (name "Net-(D36-DO)") (class "Default")
      (node (ref "D36") (pin "SDO") (pinfunction "DO_SDO") (pintype "bidirectional"))
      (node (ref "D37") (pin "SDI") (pinfunction "DI_SDI") (pintype "bidirectional"))
    )
    (net (code "77") (name "Net-(D37-CO)") (class "Default")
      (node (ref "D37") (pin "CKO") (pinfunction "CO_CKO") (pintype "bidirectional"))
      (node (ref "D38") (pin "CKI") (pinfunction "CI_CKI") (pintype "bidirectional"))
    )
    (net (code "78") (name "Net-(D37-DO)") (class "Default")
      (node (ref "D37") (pin "SDO") (pinfunction "DO_SDO") (pintype "bidirectional"))
      (node (ref "D38") (pin "SDI") (pinfunction "DI_SDI") (pintype "bidirectional"))
    )
    (net (code "79") (name "Net-(D38-CO)") (class "Default")
      (node (ref "D38") (pin "CKO") (pinfunction "CO_CKO") (pintype "bidirectional"))
      (node (ref "D39") (pin "CKI") (pinfunction "CI_CKI") (pintype "bidirectional"))
    )
    (net (code "80") (name "Net-(D38-DO)") (class "Default")
      (node (ref "D38") (pin "SDO") (pinfunction "DO_SDO") (pintype "bidirectional"))
      (node (ref "D39") (pin "SDI") (pinfunction "DI_SDI") (pintype "bidirectional"))
    )
    (net (code "81") (name "Net-(D39-CO)") (class "Default")
      (node (ref "D39") (pin "CKO") (pinfunction "CO_CKO") (pintype "bidirectional"))
      (node (ref "D40") (pin "CKI") (pinfunction "CI_CKI") (pintype "bidirectional"))
    )
    (net (code "82") (name "Net-(D39-DO)") (class "Default")
      (node (ref "D39") (pin "SDO") (pinfunction "DO_SDO") (pintype "bidirectional"))
      (node (ref "D40") (pin "SDI") (pinfunction "DI_SDI") (pintype "bidirectional"))
    )
    (net (code "83") (name "Net-(D40-CO)") (class "Default")
      (node (ref "D40") (pin "CKO") (pinfunction "CO_CKO") (pintype "bidirectional"))
      (node (ref "J3") (pin "P$2") (pinfunction "2_P$2") (pintype "passive"))
    )
    (net (code "84") (name "Net-(D40-DO)") (class "Default")
      (node (ref "D40") (pin "SDO") (pinfunction "DO_SDO") (pintype "bidirectional"))
      (node (ref "J3") (pin "P$1") (pinfunction "1_P$1") (pintype "passive"))
    )
  )
)
